# Omega2-IO-Power-Full.net
KiCad netlist of a schematic drawn in EAGLE
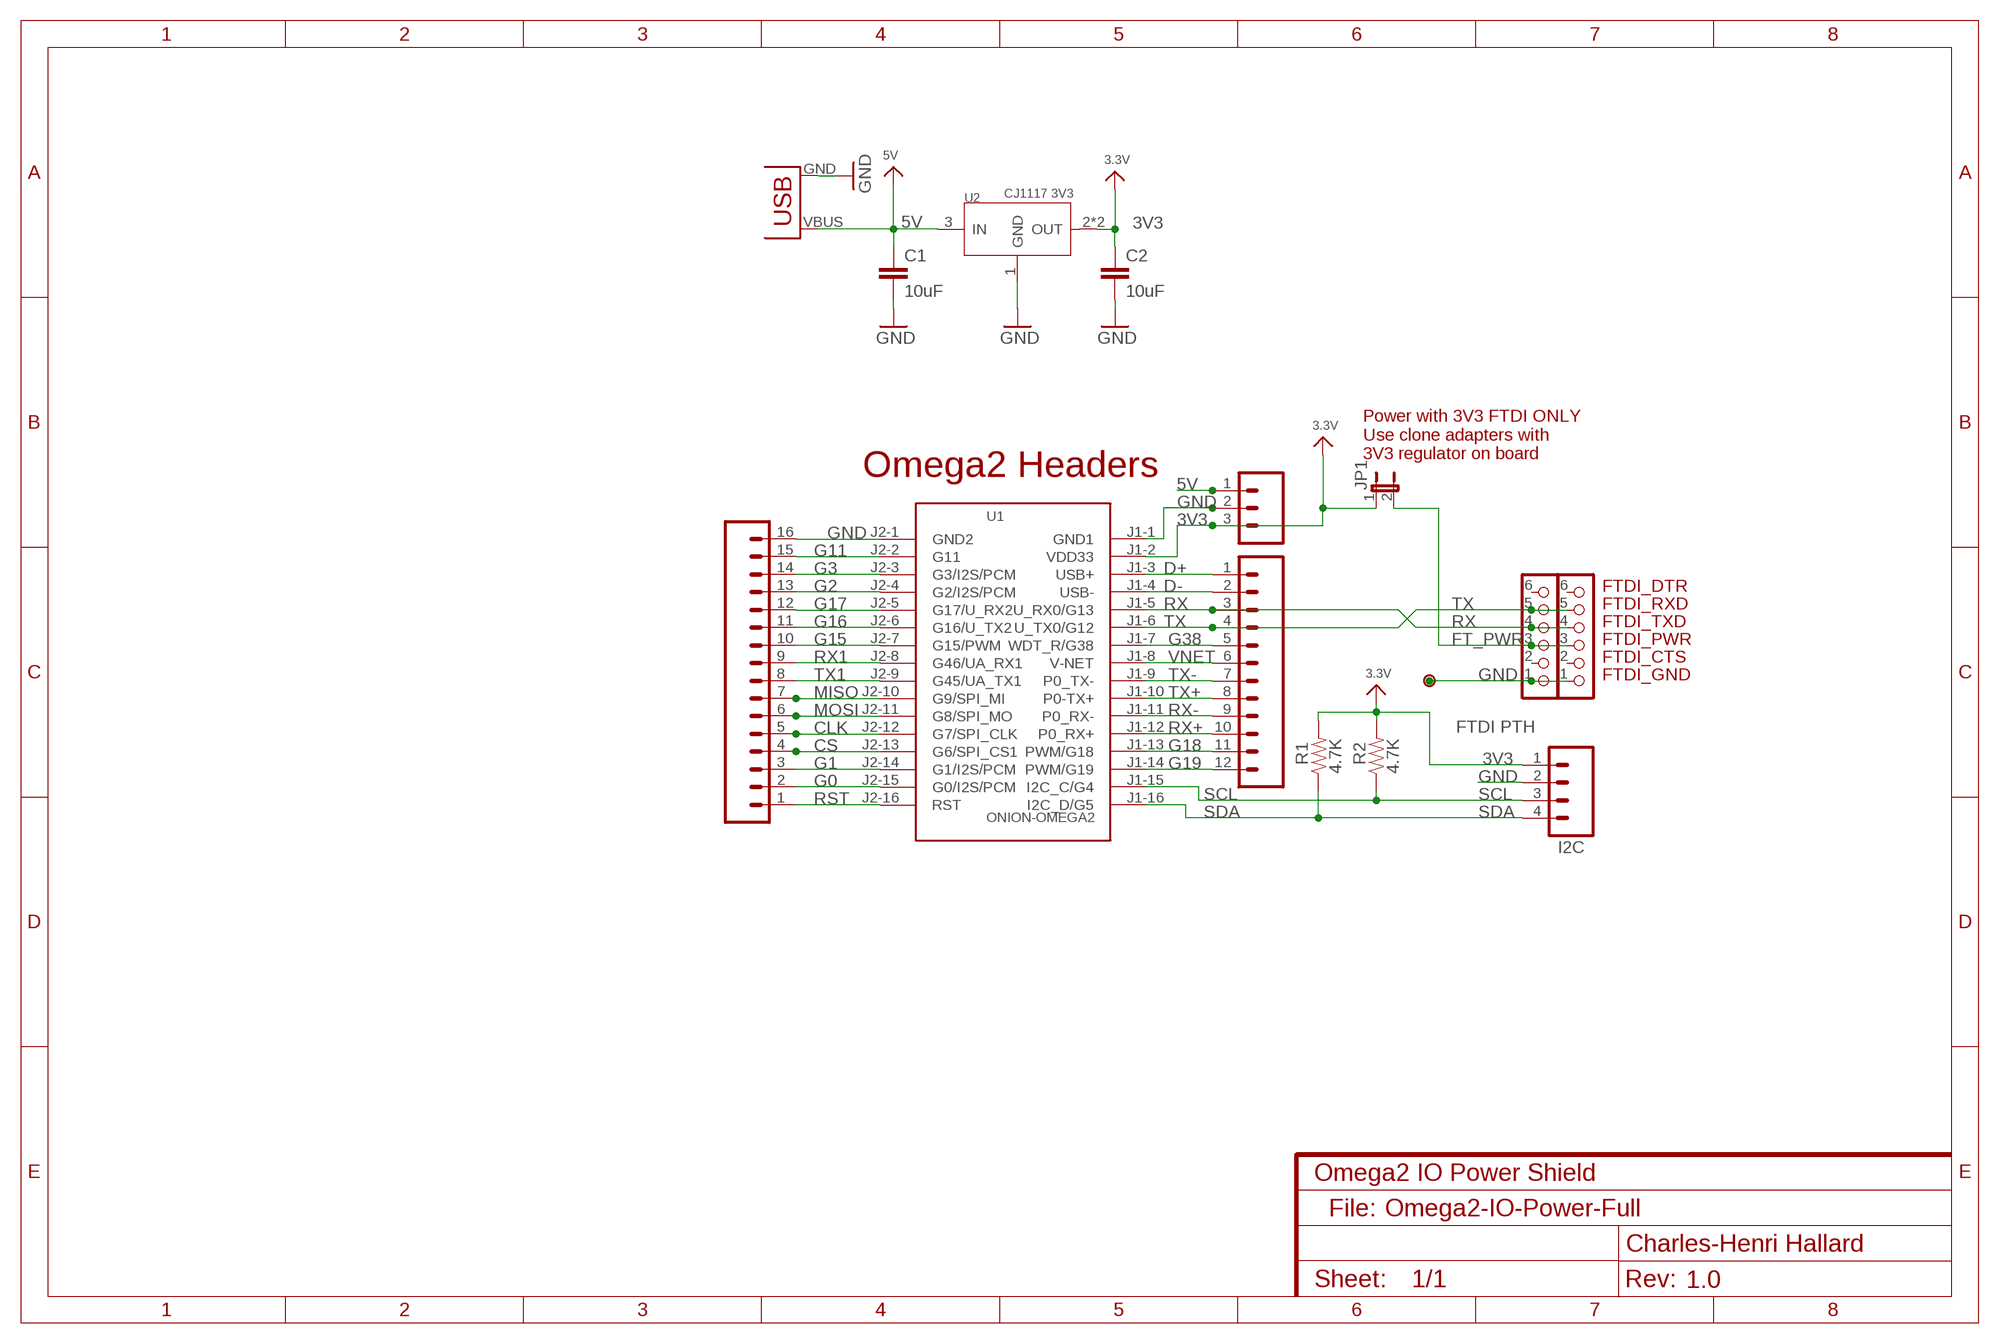
[diagram p0: schematic, sheet 1]

(export (version "E")
  (design (tool "Eeschema 10.0.6"))
  (components
    (comp (ref "C1")
      (value "10uF")
      (footprint "eagle-import:0805-CAP-LARGEPADS")
      (libsource (lib "eagle-import") (part "CAP0805-CAP-LARGEPADS"))
    )
    (comp (ref "C2")
      (value "10uF")
      (footprint "eagle-import:0805-CAP-LARGEPADS")
      (libsource (lib "eagle-import") (part "CAP0805-CAP-LARGEPADS"))
    )
    (comp (ref "FTDI")
      (value "CON_HEADER_1X06-PTH")
      (footprint "eagle-import:M1X6")
      (libsource (lib "eagle-import") (part "CON_HEADER_1X06-PTH"))
    )
    (comp (ref "I2C")
      (value "M04PTH")
      (footprint "eagle-import:1X04")
      (libsource (lib "eagle-import") (part "M04PTH"))
    )
    (comp (ref "J1")
      (value "M16PTH")
      (footprint "eagle-import:1X16")
      (libsource (lib "eagle-import") (part "M16PTH"))
    )
    (comp (ref "J2")
      (value "M12PTH")
      (footprint "eagle-import:1X12")
      (libsource (lib "eagle-import") (part "M12PTH"))
    )
    (comp (ref "J7")
      (value "M03PTH")
      (footprint "eagle-import:1X03")
      (libsource (lib "eagle-import") (part "M03PTH"))
    )
    (comp (ref "JP1")
      (value "JUMPER2")
      (footprint "eagle-import:JUMPER2")
      (libsource (lib "eagle-import") (part "JUMPER2"))
    )
    (comp (ref "P2")
      (value "PADNORMAL")
      (footprint "eagle-import:PAD")
      (libsource (lib "eagle-import") (part "PADNORMAL"))
    )
    (comp (ref "PTH")
      (value "CON_HEADER_1X06")
      (footprint "eagle-import:M1X6_MALE_RIGHT_ANGLED_SMD_NO_HOLES")
      (libsource (lib "eagle-import") (part "CON_HEADER_1X06"))
    )
    (comp (ref "R1")
      (value "4.7K")
      (footprint "eagle-import:0805-RES")
      (libsource (lib "eagle-import") (part "RESISTOR0805-RES"))
    )
    (comp (ref "R2")
      (value "4.7K")
      (footprint "eagle-import:0805-RES")
      (libsource (lib "eagle-import") (part "RESISTOR0805-RES"))
    )
    (comp (ref "U1")
      (value "ONION-OMEGA2")
      (footprint "eagle-import:ONION-2MM-2X16")
      (libsource (lib "eagle-import") (part "ONION-OMEGA2"))
    )
    (comp (ref "U2")
      (value "CJ1117 3V3")
      (footprint "eagle-import:SOT89")
      (libsource (lib "eagle-import") (part "CJ1117-3.3-1310120P1"))
    )
    (comp (ref "USB")
      (value "USB_POWER")
      (footprint "eagle-import:USB_MINIB_POWER")
      (libsource (lib "eagle-import") (part "USB_POWER"))
    )
  )
  (nets
    (net (code "1") (name "/CLK") (class "Default")
      (node (ref "J1") (pin "5") (pinfunction "5_5") (pintype "passive"))
      (node (ref "U1") (pin "J2-12") (pinfunction "G7/SPI_CLK_J2-12") (pintype "bidirectional"))
    )
    (net (code "2") (name "/CS") (class "Default")
      (node (ref "J1") (pin "4") (pinfunction "4_4") (pintype "passive"))
      (node (ref "U1") (pin "J2-13") (pinfunction "G6/SPI_CS1_J2-13") (pintype "bidirectional"))
    )
    (net (code "3") (name "/D+") (class "Default")
      (node (ref "J2") (pin "1") (pinfunction "1_1") (pintype "passive"))
      (node (ref "U1") (pin "J1-3") (pinfunction "USB+_J1-3") (pintype "bidirectional"))
    )
    (net (code "4") (name "/D-") (class "Default")
      (node (ref "J2") (pin "2") (pinfunction "2_2") (pintype "passive"))
      (node (ref "U1") (pin "J1-4") (pinfunction "USB-_J1-4") (pintype "bidirectional"))
    )
    (net (code "5") (name "/FT_PWR") (class "Default")
      (node (ref "FTDI") (pin "3") (pinfunction "3_3") (pintype "passive"))
      (node (ref "JP1") (pin "2") (pinfunction "2_2") (pintype "passive"))
      (node (ref "PTH") (pin "3") (pinfunction "3_3") (pintype "passive"))
    )
    (net (code "6") (name "/G0") (class "Default")
      (node (ref "J1") (pin "2") (pinfunction "2_2") (pintype "passive"))
      (node (ref "U1") (pin "J2-15") (pinfunction "G0/I2S/PCM_J2-15") (pintype "bidirectional"))
    )
    (net (code "7") (name "/G1") (class "Default")
      (node (ref "J1") (pin "3") (pinfunction "3_3") (pintype "passive"))
      (node (ref "U1") (pin "J2-14") (pinfunction "G1/I2S/PCM_J2-14") (pintype "bidirectional"))
    )
    (net (code "8") (name "/G2") (class "Default")
      (node (ref "J1") (pin "13") (pinfunction "13_13") (pintype "passive"))
      (node (ref "U1") (pin "J2-4") (pinfunction "G2/I2S/PCM_J2-4") (pintype "bidirectional"))
    )
    (net (code "9") (name "/G3") (class "Default")
      (node (ref "J1") (pin "14") (pinfunction "14_14") (pintype "passive"))
      (node (ref "U1") (pin "J2-3") (pinfunction "G3/I2S/PCM_J2-3") (pintype "bidirectional"))
    )
    (net (code "10") (name "/G11") (class "Default")
      (node (ref "J1") (pin "15") (pinfunction "15_15") (pintype "passive"))
      (node (ref "U1") (pin "J2-2") (pinfunction "G11_J2-2") (pintype "bidirectional"))
    )
    (net (code "11") (name "/G15") (class "Default")
      (node (ref "J1") (pin "10") (pinfunction "10_10") (pintype "passive"))
      (node (ref "U1") (pin "J2-7") (pinfunction "G15/PWM_J2-7") (pintype "bidirectional"))
    )
    (net (code "12") (name "/G16") (class "Default")
      (node (ref "J1") (pin "11") (pinfunction "11_11") (pintype "passive"))
      (node (ref "U1") (pin "J2-6") (pinfunction "G16/U_TX2_J2-6") (pintype "bidirectional"))
    )
    (net (code "13") (name "/G17") (class "Default")
      (node (ref "J1") (pin "12") (pinfunction "12_12") (pintype "passive"))
      (node (ref "U1") (pin "J2-5") (pinfunction "G17/U_RX2_J2-5") (pintype "bidirectional"))
    )
    (net (code "14") (name "/G18") (class "Default")
      (node (ref "J2") (pin "11") (pinfunction "11_11") (pintype "passive"))
      (node (ref "U1") (pin "J1-13") (pinfunction "PWM/G18_J1-13") (pintype "bidirectional"))
    )
    (net (code "15") (name "/G19") (class "Default")
      (node (ref "J2") (pin "12") (pinfunction "12_12") (pintype "passive"))
      (node (ref "U1") (pin "J1-14") (pinfunction "PWM/G19_J1-14") (pintype "bidirectional"))
    )
    (net (code "16") (name "/G38") (class "Default")
      (node (ref "J2") (pin "5") (pinfunction "5_5") (pintype "passive"))
      (node (ref "U1") (pin "J1-7") (pinfunction "WDT_R/G38_J1-7") (pintype "bidirectional"))
    )
    (net (code "17") (name "/MISO") (class "Default")
      (node (ref "J1") (pin "7") (pinfunction "7_7") (pintype "passive"))
      (node (ref "U1") (pin "J2-10") (pinfunction "G9/SPI_MI_J2-10") (pintype "bidirectional"))
    )
    (net (code "18") (name "/MOSI") (class "Default")
      (node (ref "J1") (pin "6") (pinfunction "6_6") (pintype "passive"))
      (node (ref "U1") (pin "J2-11") (pinfunction "G8/SPI_MO_J2-11") (pintype "bidirectional"))
    )
    (net (code "19") (name "/RST") (class "Default")
      (node (ref "J1") (pin "1") (pinfunction "1_1") (pintype "passive"))
      (node (ref "U1") (pin "J2-16") (pinfunction "RST_J2-16") (pintype "bidirectional"))
    )
    (net (code "20") (name "/RX") (class "Default")
      (node (ref "FTDI") (pin "4") (pinfunction "4_4") (pintype "passive"))
      (node (ref "J2") (pin "3") (pinfunction "3_3") (pintype "passive"))
      (node (ref "PTH") (pin "4") (pinfunction "4_4") (pintype "passive"))
      (node (ref "U1") (pin "J1-5") (pinfunction "U_RX0/G13_J1-5") (pintype "bidirectional"))
    )
    (net (code "21") (name "/RX+") (class "Default")
      (node (ref "J2") (pin "10") (pinfunction "10_10") (pintype "passive"))
      (node (ref "U1") (pin "J1-12") (pinfunction "P0_RX+_J1-12") (pintype "bidirectional"))
    )
    (net (code "22") (name "/RX-") (class "Default")
      (node (ref "J2") (pin "9") (pinfunction "9_9") (pintype "passive"))
      (node (ref "U1") (pin "J1-11") (pinfunction "P0_RX-_J1-11") (pintype "bidirectional"))
    )
    (net (code "23") (name "/RX1") (class "Default")
      (node (ref "J1") (pin "9") (pinfunction "9_9") (pintype "passive"))
      (node (ref "U1") (pin "J2-8") (pinfunction "G46/UA_RX1_J2-8") (pintype "bidirectional"))
    )
    (net (code "24") (name "/SCL") (class "Default")
      (node (ref "I2C") (pin "3") (pinfunction "3_3") (pintype "passive"))
      (node (ref "R2") (pin "1") (pinfunction "1_1") (pintype "passive"))
      (node (ref "U1") (pin "J1-15") (pinfunction "I2C_C/G4_J1-15") (pintype "bidirectional"))
    )
    (net (code "25") (name "/SDA") (class "Default")
      (node (ref "I2C") (pin "4") (pinfunction "4_4") (pintype "passive"))
      (node (ref "R1") (pin "1") (pinfunction "1_1") (pintype "passive"))
      (node (ref "U1") (pin "J1-16") (pinfunction "I2C_D/G5_J1-16") (pintype "bidirectional"))
    )
    (net (code "26") (name "/TX") (class "Default")
      (node (ref "FTDI") (pin "5") (pinfunction "5_5") (pintype "passive"))
      (node (ref "J2") (pin "4") (pinfunction "4_4") (pintype "passive"))
      (node (ref "PTH") (pin "5") (pinfunction "5_5") (pintype "passive"))
      (node (ref "U1") (pin "J1-6") (pinfunction "U_TX0/G12_J1-6") (pintype "bidirectional"))
    )
    (net (code "27") (name "/TX+") (class "Default")
      (node (ref "J2") (pin "8") (pinfunction "8_8") (pintype "passive"))
      (node (ref "U1") (pin "J1-10") (pinfunction "P0-TX+_J1-10") (pintype "bidirectional"))
    )
    (net (code "28") (name "/TX-") (class "Default")
      (node (ref "J2") (pin "7") (pinfunction "7_7") (pintype "passive"))
      (node (ref "U1") (pin "J1-9") (pinfunction "P0_TX-_J1-9") (pintype "bidirectional"))
    )
    (net (code "29") (name "/TX1") (class "Default")
      (node (ref "J1") (pin "8") (pinfunction "8_8") (pintype "passive"))
      (node (ref "U1") (pin "J2-9") (pinfunction "G45/UA_TX1_J2-9") (pintype "bidirectional"))
    )
    (net (code "30") (name "/VNET") (class "Default")
      (node (ref "J2") (pin "6") (pinfunction "6_6") (pintype "passive"))
      (node (ref "U1") (pin "J1-8") (pinfunction "V-NET_J1-8") (pintype "bidirectional"))
    )
    (net (code "31") (name "3.3V") (class "Default")
      (node (ref "C2") (pin "1") (pinfunction "1_1") (pintype "passive"))
      (node (ref "I2C") (pin "1") (pinfunction "1_1") (pintype "passive"))
      (node (ref "J7") (pin "3") (pinfunction "3_3") (pintype "passive"))
      (node (ref "JP1") (pin "1") (pinfunction "1_1") (pintype "passive"))
      (node (ref "R1") (pin "2") (pinfunction "2_2") (pintype "passive"))
      (node (ref "R2") (pin "2") (pinfunction "2_2") (pintype "passive"))
      (node (ref "U1") (pin "J1-2") (pinfunction "VDD33_J1-2") (pintype "bidirectional"))
      (node (ref "U2") (pin "2") (pinfunction "OUT_2") (pintype "bidirectional"))
      (node (ref "U2") (pin "4") (pinfunction "OUT_4") (pintype "bidirectional"))
    )
    (net (code "32") (name "5V") (class "Default")
      (node (ref "C1") (pin "1") (pinfunction "1_1") (pintype "passive"))
      (node (ref "J7") (pin "1") (pinfunction "1_1") (pintype "passive"))
      (node (ref "U2") (pin "3") (pinfunction "IN_3") (pintype "bidirectional"))
      (node (ref "USB") (pin "VBUS") (pinfunction "VCC_VBUS") (pintype "bidirectional"))
    )
    (net (code "33") (name "GND") (class "Default")
      (node (ref "C1") (pin "2") (pinfunction "2_2") (pintype "passive"))
      (node (ref "C2") (pin "2") (pinfunction "2_2") (pintype "passive"))
      (node (ref "FTDI") (pin "1") (pinfunction "1_1") (pintype "bidirectional"))
      (node (ref "I2C") (pin "2") (pinfunction "2_2") (pintype "passive"))
      (node (ref "J1") (pin "16") (pinfunction "16_16") (pintype "passive"))
      (node (ref "J7") (pin "2") (pinfunction "2_2") (pintype "passive"))
      (node (ref "P2") (pin "1") (pinfunction "1_1") (pintype "bidirectional"))
      (node (ref "PTH") (pin "1") (pinfunction "1_1") (pintype "bidirectional"))
      (node (ref "U1") (pin "J1-1") (pinfunction "GND1_J1-1") (pintype "bidirectional"))
      (node (ref "U1") (pin "J2-1") (pinfunction "GND2_J2-1") (pintype "bidirectional"))
      (node (ref "U2") (pin "1") (pinfunction "GND_1") (pintype "bidirectional"))
      (node (ref "USB") (pin "GND") (pinfunction "GND_GND") (pintype "bidirectional"))
    )
    (net (code "34") (name "unconnected-(FTDI-Pad2)") (class "Default")
      (node (ref "FTDI") (pin "2") (pinfunction "2_2") (pintype "bidirectional"))
    )
    (net (code "35") (name "unconnected-(FTDI-Pad6)") (class "Default")
      (node (ref "FTDI") (pin "6") (pinfunction "6_6") (pintype "passive"))
    )
    (net (code "36") (name "unconnected-(PTH-Pad2)") (class "Default")
      (node (ref "PTH") (pin "2") (pinfunction "2_2") (pintype "bidirectional"))
    )
    (net (code "37") (name "unconnected-(PTH-Pad6)") (class "Default")
      (node (ref "PTH") (pin "6") (pinfunction "6_6") (pintype "passive"))
    )
  )
)
